# Signal_processing.net
KiCad netlist of a schematic drawn in EAGLE
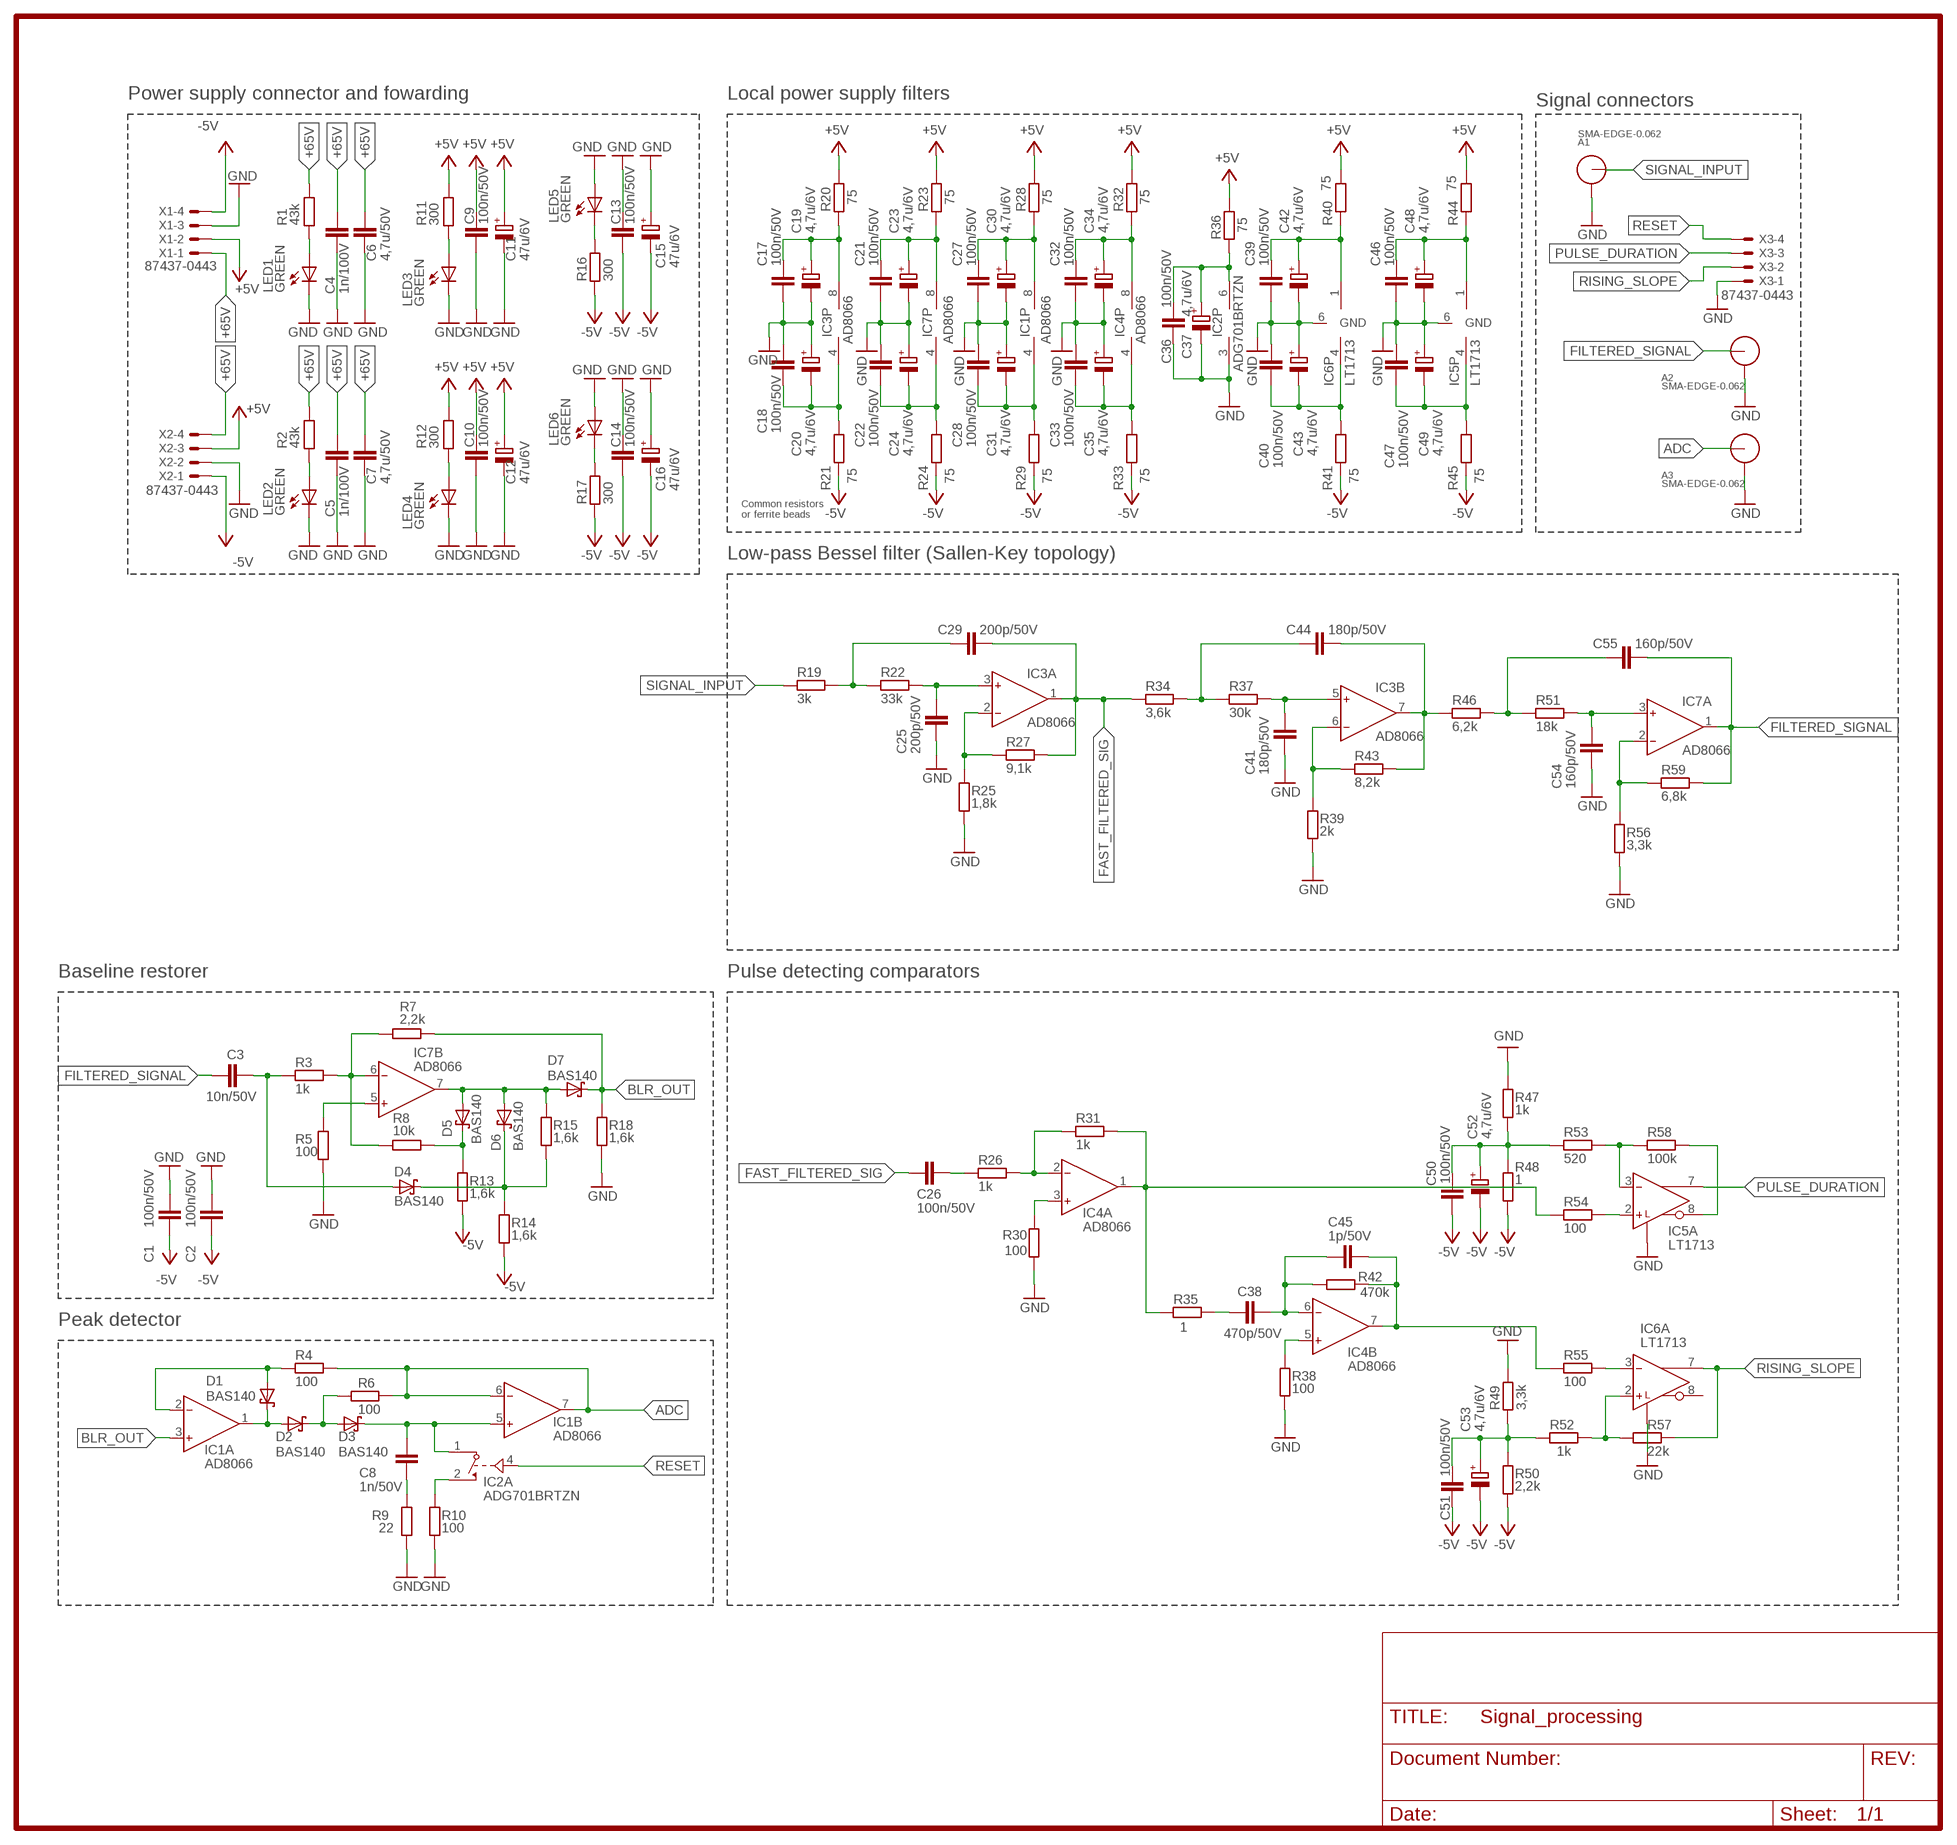
[diagram p0: schematic, sheet 1]

(export (version "E")
  (design (tool "Eeschema 10.0.6"))
  (components
    (comp (ref "A1")
      (value "SMA-EDGE-0.062")
      (footprint "eagle-import:CONSMA003.062")
      (libsource (lib "eagle-import") (part "LINX-SMA-EDGE-0.062"))
    )
    (comp (ref "A2")
      (value "SMA-EDGE-0.062")
      (footprint "eagle-import:CONSMA003.062")
      (libsource (lib "eagle-import") (part "LINX-SMA-EDGE-0.062"))
    )
    (comp (ref "A3")
      (value "SMA-EDGE-0.062")
      (footprint "eagle-import:CONSMA003.062")
      (libsource (lib "eagle-import") (part "LINX-SMA-EDGE-0.062"))
    )
    (comp (ref "C1")
      (value "100n/50V")
      (footprint "eagle-import:C0603")
      (libsource (lib "eagle-import") (part "rcl_334_C-EUC0603"))
    )
    (comp (ref "C2")
      (value "100n/50V")
      (footprint "eagle-import:C0603")
      (libsource (lib "eagle-import") (part "rcl_334_C-EUC0603"))
    )
    (comp (ref "C3")
      (value "10n/50V")
      (footprint "eagle-import:C0603")
      (libsource (lib "eagle-import") (part "rcl_334_C-EUC0603"))
    )
    (comp (ref "C4")
      (value "1n/100V")
      (footprint "eagle-import:C0603")
      (libsource (lib "eagle-import") (part "C-EUC0603"))
    )
    (comp (ref "C5")
      (value "1n/100V")
      (footprint "eagle-import:C0603")
      (libsource (lib "eagle-import") (part "C-EUC0603"))
    )
    (comp (ref "C6")
      (value "4,7u/50V")
      (footprint "eagle-import:C1206")
      (libsource (lib "eagle-import") (part "rcl_334_C-EUC1206"))
    )
    (comp (ref "C7")
      (value "4,7u/50V")
      (footprint "eagle-import:C1206")
      (libsource (lib "eagle-import") (part "rcl_334_C-EUC1206"))
    )
    (comp (ref "C8")
      (value "1n/50V")
      (footprint "eagle-import:C0603")
      (libsource (lib "eagle-import") (part "rcl_334_C-EUC0603"))
    )
    (comp (ref "C9")
      (value "100n/50V")
      (footprint "eagle-import:C0603")
      (libsource (lib "eagle-import") (part "rcl_334_C-EUC0603"))
    )
    (comp (ref "C10")
      (value "100n/50V")
      (footprint "eagle-import:C0603")
      (libsource (lib "eagle-import") (part "rcl_334_C-EUC0603"))
    )
    (comp (ref "C11")
      (value "47u/6V")
      (footprint "eagle-import:SMC_B")
      (libsource (lib "eagle-import") (part "CPOL-EUSMCB"))
    )
    (comp (ref "C12")
      (value "47u/6V")
      (footprint "eagle-import:SMC_B")
      (libsource (lib "eagle-import") (part "CPOL-EUSMCB"))
    )
    (comp (ref "C13")
      (value "100n/50V")
      (footprint "eagle-import:C0603")
      (libsource (lib "eagle-import") (part "rcl_334_C-EUC0603"))
    )
    (comp (ref "C14")
      (value "100n/50V")
      (footprint "eagle-import:C0603")
      (libsource (lib "eagle-import") (part "rcl_334_C-EUC0603"))
    )
    (comp (ref "C15")
      (value "47u/6V")
      (footprint "eagle-import:SMC_B")
      (libsource (lib "eagle-import") (part "CPOL-EUSMCB"))
    )
    (comp (ref "C16")
      (value "47u/6V")
      (footprint "eagle-import:SMC_B")
      (libsource (lib "eagle-import") (part "CPOL-EUSMCB"))
    )
    (comp (ref "C17")
      (value "100n/50V")
      (footprint "eagle-import:C0603")
      (libsource (lib "eagle-import") (part "rcl_334_C-EUC0603"))
    )
    (comp (ref "C18")
      (value "100n/50V")
      (footprint "eagle-import:C0603")
      (libsource (lib "eagle-import") (part "rcl_334_C-EUC0603"))
    )
    (comp (ref "C19")
      (value "4,7u/6V")
      (footprint "eagle-import:SMC_A")
      (libsource (lib "eagle-import") (part "CPOL-EUSMCA"))
    )
    (comp (ref "C20")
      (value "4,7u/6V")
      (footprint "eagle-import:SMC_A")
      (libsource (lib "eagle-import") (part "CPOL-EUSMCA"))
    )
    (comp (ref "C21")
      (value "100n/50V")
      (footprint "eagle-import:C0603")
      (libsource (lib "eagle-import") (part "rcl_334_C-EUC0603"))
    )
    (comp (ref "C22")
      (value "100n/50V")
      (footprint "eagle-import:C0603")
      (libsource (lib "eagle-import") (part "rcl_334_C-EUC0603"))
    )
    (comp (ref "C23")
      (value "4,7u/6V")
      (footprint "eagle-import:SMC_A")
      (libsource (lib "eagle-import") (part "CPOL-EUSMCA"))
    )
    (comp (ref "C24")
      (value "4,7u/6V")
      (footprint "eagle-import:SMC_A")
      (libsource (lib "eagle-import") (part "CPOL-EUSMCA"))
    )
    (comp (ref "C25")
      (value "200p/50V")
      (footprint "eagle-import:C0603")
      (libsource (lib "eagle-import") (part "rcl_334_C-EUC0603"))
    )
    (comp (ref "C26")
      (value "100n/50V")
      (footprint "eagle-import:C0603")
      (libsource (lib "eagle-import") (part "rcl_334_C-EUC0603"))
    )
    (comp (ref "C27")
      (value "100n/50V")
      (footprint "eagle-import:C0603")
      (libsource (lib "eagle-import") (part "rcl_334_C-EUC0603"))
    )
    (comp (ref "C28")
      (value "100n/50V")
      (footprint "eagle-import:C0603")
      (libsource (lib "eagle-import") (part "rcl_334_C-EUC0603"))
    )
    (comp (ref "C29")
      (value "200p/50V")
      (footprint "eagle-import:C0603")
      (libsource (lib "eagle-import") (part "rcl_334_C-EUC0603"))
    )
    (comp (ref "C30")
      (value "4,7u/6V")
      (footprint "eagle-import:SMC_A")
      (libsource (lib "eagle-import") (part "CPOL-EUSMCA"))
    )
    (comp (ref "C31")
      (value "4,7u/6V")
      (footprint "eagle-import:SMC_A")
      (libsource (lib "eagle-import") (part "CPOL-EUSMCA"))
    )
    (comp (ref "C32")
      (value "100n/50V")
      (footprint "eagle-import:C0603")
      (libsource (lib "eagle-import") (part "rcl_334_C-EUC0603"))
    )
    (comp (ref "C33")
      (value "100n/50V")
      (footprint "eagle-import:C0603")
      (libsource (lib "eagle-import") (part "rcl_334_C-EUC0603"))
    )
    (comp (ref "C34")
      (value "4,7u/6V")
      (footprint "eagle-import:SMC_A")
      (libsource (lib "eagle-import") (part "CPOL-EUSMCA"))
    )
    (comp (ref "C35")
      (value "4,7u/6V")
      (footprint "eagle-import:SMC_A")
      (libsource (lib "eagle-import") (part "CPOL-EUSMCA"))
    )
    (comp (ref "C36")
      (value "100n/50V")
      (footprint "eagle-import:C0603")
      (libsource (lib "eagle-import") (part "rcl_334_C-EUC0603"))
    )
    (comp (ref "C37")
      (value "4,7u/6V")
      (footprint "eagle-import:SMC_A")
      (libsource (lib "eagle-import") (part "CPOL-EUSMCA"))
    )
    (comp (ref "C38")
      (value "470p/50V")
      (footprint "eagle-import:C0603")
      (libsource (lib "eagle-import") (part "rcl_334_C-EUC0603"))
    )
    (comp (ref "C39")
      (value "100n/50V")
      (footprint "eagle-import:C0603")
      (libsource (lib "eagle-import") (part "rcl_334_C-EUC0603"))
    )
    (comp (ref "C40")
      (value "100n/50V")
      (footprint "eagle-import:C0603")
      (libsource (lib "eagle-import") (part "rcl_334_C-EUC0603"))
    )
    (comp (ref "C41")
      (value "180p/50V")
      (footprint "eagle-import:C0603")
      (libsource (lib "eagle-import") (part "rcl_334_C-EUC0603"))
    )
    (comp (ref "C42")
      (value "4,7u/6V")
      (footprint "eagle-import:SMC_A")
      (libsource (lib "eagle-import") (part "CPOL-EUSMCA"))
    )
    (comp (ref "C43")
      (value "4,7u/6V")
      (footprint "eagle-import:SMC_A")
      (libsource (lib "eagle-import") (part "CPOL-EUSMCA"))
    )
    (comp (ref "C44")
      (value "180p/50V")
      (footprint "eagle-import:C0603")
      (libsource (lib "eagle-import") (part "rcl_334_C-EUC0603"))
    )
    (comp (ref "C45")
      (value "1p/50V")
      (footprint "eagle-import:C0603")
      (libsource (lib "eagle-import") (part "rcl_334_C-EUC0603"))
    )
    (comp (ref "C46")
      (value "100n/50V")
      (footprint "eagle-import:C0603")
      (libsource (lib "eagle-import") (part "rcl_334_C-EUC0603"))
    )
    (comp (ref "C47")
      (value "100n/50V")
      (footprint "eagle-import:C0603")
      (libsource (lib "eagle-import") (part "rcl_334_C-EUC0603"))
    )
    (comp (ref "C48")
      (value "4,7u/6V")
      (footprint "eagle-import:SMC_A")
      (libsource (lib "eagle-import") (part "CPOL-EUSMCA"))
    )
    (comp (ref "C49")
      (value "4,7u/6V")
      (footprint "eagle-import:SMC_A")
      (libsource (lib "eagle-import") (part "CPOL-EUSMCA"))
    )
    (comp (ref "C50")
      (value "100n/50V")
      (footprint "eagle-import:C0603")
      (libsource (lib "eagle-import") (part "rcl_334_C-EUC0603"))
    )
    (comp (ref "C51")
      (value "100n/50V")
      (footprint "eagle-import:C0603")
      (libsource (lib "eagle-import") (part "rcl_334_C-EUC0603"))
    )
    (comp (ref "C52")
      (value "4,7u/6V")
      (footprint "eagle-import:SMC_A")
      (libsource (lib "eagle-import") (part "CPOL-EUSMCA"))
    )
    (comp (ref "C53")
      (value "4,7u/6V")
      (footprint "eagle-import:SMC_A")
      (libsource (lib "eagle-import") (part "CPOL-EUSMCA"))
    )
    (comp (ref "C54")
      (value "160p/50V")
      (footprint "eagle-import:C0603")
      (libsource (lib "eagle-import") (part "rcl_334_C-EUC0603"))
    )
    (comp (ref "C55")
      (value "160p/50V")
      (footprint "eagle-import:C0603")
      (libsource (lib "eagle-import") (part "rcl_334_C-EUC0603"))
    )
    (comp (ref "D1")
      (value "BAS140")
      (footprint "eagle-import:SOD2514X100N")
      (libsource (lib "eagle-import") (part "BAS140"))
    )
    (comp (ref "D2")
      (value "BAS140")
      (footprint "eagle-import:SOD2514X100N")
      (libsource (lib "eagle-import") (part "BAS140"))
    )
    (comp (ref "D3")
      (value "BAS140")
      (footprint "eagle-import:SOD2514X100N")
      (libsource (lib "eagle-import") (part "BAS140"))
    )
    (comp (ref "D4")
      (value "BAS140")
      (footprint "eagle-import:SOD2514X100N")
      (libsource (lib "eagle-import") (part "BAS140"))
    )
    (comp (ref "D5")
      (value "BAS140")
      (footprint "eagle-import:SOD2514X100N")
      (libsource (lib "eagle-import") (part "BAS140"))
    )
    (comp (ref "D6")
      (value "BAS140")
      (footprint "eagle-import:SOD2514X100N")
      (libsource (lib "eagle-import") (part "BAS140"))
    )
    (comp (ref "D7")
      (value "BAS140")
      (footprint "eagle-import:SOD2514X100N")
      (libsource (lib "eagle-import") (part "BAS140"))
    )
    (comp (ref "IC1")
      (value "AD8066")
      (footprint "eagle-import:MSOP8")
      (libsource (lib "eagle-import") (part "AD8066"))
    )
    (comp (ref "IC2")
      (value "ADG701BRTZN")
      (footprint "eagle-import:SOT23-6")
      (libsource (lib "eagle-import") (part "ADG701BRTZN"))
    )
    (comp (ref "IC3")
      (value "AD8066")
      (footprint "eagle-import:MSOP8")
      (libsource (lib "eagle-import") (part "AD8066"))
    )
    (comp (ref "IC4")
      (value "AD8066")
      (footprint "eagle-import:MSOP8")
      (libsource (lib "eagle-import") (part "AD8066"))
    )
    (comp (ref "IC5")
      (value "LT1713")
      (footprint "eagle-import:MSOP8")
      (libsource (lib "eagle-import") (part "LT1713"))
    )
    (comp (ref "IC6")
      (value "LT1713")
      (footprint "eagle-import:MSOP8")
      (libsource (lib "eagle-import") (part "LT1713"))
    )
    (comp (ref "IC7")
      (value "AD8066")
      (footprint "eagle-import:MSOP8")
      (libsource (lib "eagle-import") (part "AD8066"))
    )
    (comp (ref "LED1")
      (value "GREEN")
      (footprint "eagle-import:CHIPLED_0603")
      (libsource (lib "eagle-import") (part "LEDCHIPLED_0603"))
    )
    (comp (ref "LED2")
      (value "GREEN")
      (footprint "eagle-import:CHIPLED_0603")
      (libsource (lib "eagle-import") (part "LEDCHIPLED_0603"))
    )
    (comp (ref "LED3")
      (value "GREEN")
      (footprint "eagle-import:CHIPLED_0603")
      (libsource (lib "eagle-import") (part "LEDCHIPLED_0603"))
    )
    (comp (ref "LED4")
      (value "GREEN")
      (footprint "eagle-import:CHIPLED_0603")
      (libsource (lib "eagle-import") (part "LEDCHIPLED_0603"))
    )
    (comp (ref "LED5")
      (value "GREEN")
      (footprint "eagle-import:CHIPLED_0603")
      (libsource (lib "eagle-import") (part "LEDCHIPLED_0603"))
    )
    (comp (ref "LED6")
      (value "GREEN")
      (footprint "eagle-import:CHIPLED_0603")
      (libsource (lib "eagle-import") (part "LEDCHIPLED_0603"))
    )
    (comp (ref "R1")
      (value "43k")
      (footprint "eagle-import:R0603")
      (libsource (lib "eagle-import") (part "R-EU_R0603"))
    )
    (comp (ref "R2")
      (value "43k")
      (footprint "eagle-import:R0603")
      (libsource (lib "eagle-import") (part "R-EU_R0603"))
    )
    (comp (ref "R3")
      (value "1k")
      (footprint "eagle-import:R0603")
      (libsource (lib "eagle-import") (part "R-EU_R0603"))
    )
    (comp (ref "R4")
      (value "100")
      (footprint "eagle-import:R0603")
      (libsource (lib "eagle-import") (part "R-EU_R0603"))
    )
    (comp (ref "R5")
      (value "100")
      (footprint "eagle-import:R0603")
      (libsource (lib "eagle-import") (part "R-EU_R0603"))
    )
    (comp (ref "R6")
      (value "100")
      (footprint "eagle-import:R0603")
      (libsource (lib "eagle-import") (part "R-EU_R0603"))
    )
    (comp (ref "R7")
      (value "2,2k")
      (footprint "eagle-import:R0603")
      (libsource (lib "eagle-import") (part "R-EU_R0603"))
    )
    (comp (ref "R8")
      (value "10k")
      (footprint "eagle-import:R0603")
      (libsource (lib "eagle-import") (part "R-EU_R0603"))
    )
    (comp (ref "R9")
      (value "22")
      (footprint "eagle-import:R0603")
      (libsource (lib "eagle-import") (part "R-EU_R0603"))
    )
    (comp (ref "R10")
      (value "100")
      (footprint "eagle-import:R0603")
      (libsource (lib "eagle-import") (part "R-EU_R0603"))
    )
    (comp (ref "R11")
      (value "300")
      (footprint "eagle-import:R0603")
      (libsource (lib "eagle-import") (part "R-EU_R0603"))
    )
    (comp (ref "R12")
      (value "300")
      (footprint "eagle-import:R0603")
      (libsource (lib "eagle-import") (part "R-EU_R0603"))
    )
    (comp (ref "R13")
      (value "1,6k")
      (footprint "eagle-import:R0603")
      (libsource (lib "eagle-import") (part "R-EU_R0603"))
    )
    (comp (ref "R14")
      (value "1,6k")
      (footprint "eagle-import:R0603")
      (libsource (lib "eagle-import") (part "R-EU_R0603"))
    )
    (comp (ref "R15")
      (value "1,6k")
      (footprint "eagle-import:R0603")
      (libsource (lib "eagle-import") (part "R-EU_R0603"))
    )
    (comp (ref "R16")
      (value "300")
      (footprint "eagle-import:R0603")
      (libsource (lib "eagle-import") (part "R-EU_R0603"))
    )
    (comp (ref "R17")
      (value "300")
      (footprint "eagle-import:R0603")
      (libsource (lib "eagle-import") (part "R-EU_R0603"))
    )
    (comp (ref "R18")
      (value "1,6k")
      (footprint "eagle-import:R0603")
      (libsource (lib "eagle-import") (part "R-EU_R0603"))
    )
    (comp (ref "R19")
      (value "3k")
      (footprint "eagle-import:R0603")
      (libsource (lib "eagle-import") (part "R-EU_R0603"))
    )
    (comp (ref "R20")
      (value "75")
      (footprint "eagle-import:R0603")
      (libsource (lib "eagle-import") (part "R-EU_R0603"))
    )
    (comp (ref "R21")
      (value "75")
      (footprint "eagle-import:R0603")
      (libsource (lib "eagle-import") (part "R-EU_R0603"))
    )
    (comp (ref "R22")
      (value "33k")
      (footprint "eagle-import:R0603")
      (libsource (lib "eagle-import") (part "R-EU_R0603"))
    )
    (comp (ref "R23")
      (value "75")
      (footprint "eagle-import:R0603")
      (libsource (lib "eagle-import") (part "R-EU_R0603"))
    )
    (comp (ref "R24")
      (value "75")
      (footprint "eagle-import:R0603")
      (libsource (lib "eagle-import") (part "R-EU_R0603"))
    )
    (comp (ref "R25")
      (value "1,8k")
      (footprint "eagle-import:R0603")
      (libsource (lib "eagle-import") (part "R-EU_R0603"))
    )
    (comp (ref "R26")
      (value "1k")
      (footprint "eagle-import:R0603")
      (libsource (lib "eagle-import") (part "R-EU_R0603"))
    )
    (comp (ref "R27")
      (value "9,1k")
      (footprint "eagle-import:R0603")
      (libsource (lib "eagle-import") (part "R-EU_R0603"))
    )
    (comp (ref "R28")
      (value "75")
      (footprint "eagle-import:R0603")
      (libsource (lib "eagle-import") (part "R-EU_R0603"))
    )
    (comp (ref "R29")
      (value "75")
      (footprint "eagle-import:R0603")
      (libsource (lib "eagle-import") (part "R-EU_R0603"))
    )
    (comp (ref "R30")
      (value "100")
      (footprint "eagle-import:R0603")
      (libsource (lib "eagle-import") (part "R-EU_R0603"))
    )
    (comp (ref "R31")
      (value "1k")
      (footprint "eagle-import:R0603")
      (libsource (lib "eagle-import") (part "R-EU_R0603"))
    )
    (comp (ref "R32")
      (value "75")
      (footprint "eagle-import:R0603")
      (libsource (lib "eagle-import") (part "R-EU_R0603"))
    )
    (comp (ref "R33")
      (value "75")
      (footprint "eagle-import:R0603")
      (libsource (lib "eagle-import") (part "R-EU_R0603"))
    )
    (comp (ref "R34")
      (value "3,6k")
      (footprint "eagle-import:R0603")
      (libsource (lib "eagle-import") (part "R-EU_R0603"))
    )
    (comp (ref "R35")
      (value "1")
      (footprint "eagle-import:R0603")
      (libsource (lib "eagle-import") (part "R-EU_R0603"))
    )
    (comp (ref "R36")
      (value "75")
      (footprint "eagle-import:R0603")
      (libsource (lib "eagle-import") (part "R-EU_R0603"))
    )
    (comp (ref "R37")
      (value "30k")
      (footprint "eagle-import:R0603")
      (libsource (lib "eagle-import") (part "R-EU_R0603"))
    )
    (comp (ref "R38")
      (value "100")
      (footprint "eagle-import:R0603")
      (libsource (lib "eagle-import") (part "R-EU_R0603"))
    )
    (comp (ref "R39")
      (value "2k")
      (footprint "eagle-import:R0603")
      (libsource (lib "eagle-import") (part "R-EU_R0603"))
    )
    (comp (ref "R40")
      (value "75")
      (footprint "eagle-import:R0603")
      (libsource (lib "eagle-import") (part "R-EU_R0603"))
    )
    (comp (ref "R41")
      (value "75")
      (footprint "eagle-import:R0603")
      (libsource (lib "eagle-import") (part "R-EU_R0603"))
    )
    (comp (ref "R42")
      (value "470k")
      (footprint "eagle-import:R0603")
      (libsource (lib "eagle-import") (part "R-EU_R0603"))
    )
    (comp (ref "R43")
      (value "8,2k")
      (footprint "eagle-import:R0603")
      (libsource (lib "eagle-import") (part "R-EU_R0603"))
    )
    (comp (ref "R44")
      (value "75")
      (footprint "eagle-import:R0603")
      (libsource (lib "eagle-import") (part "R-EU_R0603"))
    )
    (comp (ref "R45")
      (value "75")
      (footprint "eagle-import:R0603")
      (libsource (lib "eagle-import") (part "R-EU_R0603"))
    )
    (comp (ref "R46")
      (value "6,2k")
      (footprint "eagle-import:R0603")
      (libsource (lib "eagle-import") (part "R-EU_R0603"))
    )
    (comp (ref "R47")
      (value "1k")
      (footprint "eagle-import:R0603")
      (libsource (lib "eagle-import") (part "R-EU_R0603"))
    )
    (comp (ref "R48")
      (value "1")
      (footprint "eagle-import:R0603")
      (libsource (lib "eagle-import") (part "R-EU_R0603"))
    )
    (comp (ref "R49")
      (value "3,3k")
      (footprint "eagle-import:R0603")
      (libsource (lib "eagle-import") (part "R-EU_R0603"))
    )
    (comp (ref "R50")
      (value "2,2k")
      (footprint "eagle-import:R0603")
      (libsource (lib "eagle-import") (part "R-EU_R0603"))
    )
    (comp (ref "R51")
      (value "18k")
      (footprint "eagle-import:R0603")
      (libsource (lib "eagle-import") (part "R-EU_R0603"))
    )
    (comp (ref "R52")
      (value "1k")
      (footprint "eagle-import:R0603")
      (libsource (lib "eagle-import") (part "R-EU_R0603"))
    )
    (comp (ref "R53")
      (value "520")
      (footprint "eagle-import:R0603")
      (libsource (lib "eagle-import") (part "R-EU_R0603"))
    )
    (comp (ref "R54")
      (value "100")
      (footprint "eagle-import:R0603")
      (libsource (lib "eagle-import") (part "R-EU_R0603"))
    )
    (comp (ref "R55")
      (value "100")
      (footprint "eagle-import:R0603")
      (libsource (lib "eagle-import") (part "R-EU_R0603"))
    )
    (comp (ref "R56")
      (value "3,3k")
      (footprint "eagle-import:R0603")
      (libsource (lib "eagle-import") (part "R-EU_R0603"))
    )
    (comp (ref "R57")
      (value "22k")
      (footprint "eagle-import:R0603")
      (libsource (lib "eagle-import") (part "R-EU_R0603"))
    )
    (comp (ref "R58")
      (value "100k")
      (footprint "eagle-import:R0603")
      (libsource (lib "eagle-import") (part "R-EU_R0603"))
    )
    (comp (ref "R59")
      (value "6,8k")
      (footprint "eagle-import:R0603")
      (libsource (lib "eagle-import") (part "R-EU_R0603"))
    )
    (comp (ref "X1")
      (value "87437-0443")
      (footprint "eagle-import:87437-0443")
      (libsource (lib "eagle-import") (part "87438-0487437-0443"))
    )
    (comp (ref "X2")
      (value "87437-0443")
      (footprint "eagle-import:87437-0443")
      (libsource (lib "eagle-import") (part "87438-0487437-0443"))
    )
    (comp (ref "X3")
      (value "87437-0443")
      (footprint "eagle-import:87437-0443")
      (libsource (lib "eagle-import") (part "87438-0487437-0443"))
    )
  )
  (nets
    (net (code "1") (name "+5V") (class "Default")
      (node (ref "C10") (pin "2") (pinfunction "2_2") (pintype "passive"))
      (node (ref "C11") (pin "+") (pinfunction "+_+") (pintype "passive"))
      (node (ref "C12") (pin "+") (pinfunction "+_+") (pintype "passive"))
      (node (ref "C9") (pin "2") (pinfunction "2_2") (pintype "passive"))
      (node (ref "R11") (pin "2") (pinfunction "2_2") (pintype "passive"))
      (node (ref "R12") (pin "2") (pinfunction "2_2") (pintype "passive"))
      (node (ref "R20") (pin "1") (pinfunction "1_1") (pintype "passive"))
      (node (ref "R23") (pin "1") (pinfunction "1_1") (pintype "passive"))
      (node (ref "R28") (pin "1") (pinfunction "1_1") (pintype "passive"))
      (node (ref "R32") (pin "1") (pinfunction "1_1") (pintype "passive"))
      (node (ref "R36") (pin "1") (pinfunction "1_1") (pintype "passive"))
      (node (ref "R40") (pin "1") (pinfunction "1_1") (pintype "passive"))
      (node (ref "R44") (pin "1") (pinfunction "1_1") (pintype "passive"))
      (node (ref "X1") (pin "2") (pinfunction "S_2") (pintype "passive"))
      (node (ref "X1") (pin "6") (pinfunction "S_6") (pintype "passive"))
      (node (ref "X2") (pin "3") (pinfunction "S_3") (pintype "passive"))
      (node (ref "X2") (pin "7") (pinfunction "S_7") (pintype "passive"))
    )
    (net (code "2") (name "+65V") (class "Default")
      (node (ref "C4") (pin "2") (pinfunction "2_2") (pintype "passive"))
      (node (ref "C5") (pin "2") (pinfunction "2_2") (pintype "passive"))
      (node (ref "C6") (pin "1") (pinfunction "1_1") (pintype "passive"))
      (node (ref "C7") (pin "1") (pinfunction "1_1") (pintype "passive"))
      (node (ref "R1") (pin "2") (pinfunction "2_2") (pintype "passive"))
      (node (ref "R2") (pin "2") (pinfunction "2_2") (pintype "passive"))
      (node (ref "X1") (pin "1") (pinfunction "S_1") (pintype "passive"))
      (node (ref "X1") (pin "5") (pinfunction "S_5") (pintype "passive"))
      (node (ref "X2") (pin "4") (pinfunction "S_4") (pintype "passive"))
      (node (ref "X2") (pin "8") (pinfunction "S_8") (pintype "passive"))
    )
    (net (code "3") (name "-5V") (class "Default")
      (node (ref "C1") (pin "1") (pinfunction "1_1") (pintype "passive"))
      (node (ref "C13") (pin "1") (pinfunction "1_1") (pintype "passive"))
      (node (ref "C14") (pin "1") (pinfunction "1_1") (pintype "passive"))
      (node (ref "C15") (pin "-") (pinfunction "-_-") (pintype "passive"))
      (node (ref "C16") (pin "-") (pinfunction "-_-") (pintype "passive"))
      (node (ref "C2") (pin "1") (pinfunction "1_1") (pintype "passive"))
      (node (ref "C50") (pin "2") (pinfunction "2_2") (pintype "passive"))
      (node (ref "C51") (pin "2") (pinfunction "2_2") (pintype "passive"))
      (node (ref "C52") (pin "-") (pinfunction "-_-") (pintype "passive"))
      (node (ref "C53") (pin "-") (pinfunction "-_-") (pintype "passive"))
      (node (ref "R13") (pin "2") (pinfunction "2_2") (pintype "passive"))
      (node (ref "R14") (pin "2") (pinfunction "2_2") (pintype "passive"))
      (node (ref "R16") (pin "1") (pinfunction "1_1") (pintype "passive"))
      (node (ref "R17") (pin "1") (pinfunction "1_1") (pintype "passive"))
      (node (ref "R21") (pin "2") (pinfunction "2_2") (pintype "passive"))
      (node (ref "R24") (pin "2") (pinfunction "2_2") (pintype "passive"))
      (node (ref "R29") (pin "2") (pinfunction "2_2") (pintype "passive"))
      (node (ref "R33") (pin "2") (pinfunction "2_2") (pintype "passive"))
      (node (ref "R41") (pin "2") (pinfunction "2_2") (pintype "passive"))
      (node (ref "R45") (pin "2") (pinfunction "2_2") (pintype "passive"))
      (node (ref "R48") (pin "2") (pinfunction "2_2") (pintype "passive"))
      (node (ref "R50") (pin "2") (pinfunction "2_2") (pintype "passive"))
      (node (ref "X1") (pin "4") (pinfunction "S_4") (pintype "passive"))
      (node (ref "X1") (pin "8") (pinfunction "S_8") (pintype "passive"))
      (node (ref "X2") (pin "1") (pinfunction "S_1") (pintype "passive"))
      (node (ref "X2") (pin "5") (pinfunction "S_5") (pintype "passive"))
    )
    (net (code "4") (name "ADC") (class "Default")
      (node (ref "A3") (pin "ANT") (pinfunction "ANT_ANT") (pintype "bidirectional"))
      (node (ref "IC1") (pin "6") (pinfunction "IN-_6") (pintype "input"))
      (node (ref "IC1") (pin "7") (pinfunction "OUT_7") (pintype "output"))
      (node (ref "R4") (pin "2") (pinfunction "2_2") (pintype "passive"))
      (node (ref "R6") (pin "2") (pinfunction "2_2") (pintype "passive"))
    )
    (net (code "5") (name "BLR_OUT") (class "Default")
      (node (ref "D7") (pin "K") (pinfunction "K_K") (pintype "passive"))
      (node (ref "IC1") (pin "3") (pinfunction "IN+_3") (pintype "input"))
      (node (ref "R18") (pin "1") (pinfunction "1_1") (pintype "passive"))
      (node (ref "R7") (pin "1") (pinfunction "1_1") (pintype "passive"))
    )
    (net (code "6") (name "FAST_FILTERED_SIG") (class "Default")
      (node (ref "C26") (pin "2") (pinfunction "2_2") (pintype "passive"))
      (node (ref "C29") (pin "1") (pinfunction "1_1") (pintype "passive"))
      (node (ref "IC3") (pin "1") (pinfunction "OUT_1") (pintype "output"))
      (node (ref "R27") (pin "2") (pinfunction "2_2") (pintype "passive"))
      (node (ref "R34") (pin "1") (pinfunction "1_1") (pintype "passive"))
    )
    (net (code "7") (name "FILTERED_SIGNAL") (class "Default")
      (node (ref "A2") (pin "ANT") (pinfunction "ANT_ANT") (pintype "bidirectional"))
      (node (ref "C3") (pin "2") (pinfunction "2_2") (pintype "passive"))
      (node (ref "C55") (pin "1") (pinfunction "1_1") (pintype "passive"))
      (node (ref "IC7") (pin "1") (pinfunction "OUT_1") (pintype "output"))
      (node (ref "R59") (pin "2") (pinfunction "2_2") (pintype "passive"))
    )
    (net (code "8") (name "GND") (class "Default")
      (node (ref "A1") (pin "GND1") (pinfunction "P$2_GND1") (pintype "bidirectional"))
      (node (ref "A1") (pin "GND2") (pinfunction "P$2_GND2") (pintype "bidirectional"))
      (node (ref "A1") (pin "GND3") (pinfunction "P$2_GND3") (pintype "bidirectional"))
      (node (ref "A1") (pin "GND4") (pinfunction "P$2_GND4") (pintype "bidirectional"))
      (node (ref "A2") (pin "GND1") (pinfunction "P$2_GND1") (pintype "bidirectional"))
      (node (ref "A2") (pin "GND2") (pinfunction "P$2_GND2") (pintype "bidirectional"))
      (node (ref "A2") (pin "GND3") (pinfunction "P$2_GND3") (pintype "bidirectional"))
      (node (ref "A2") (pin "GND4") (pinfunction "P$2_GND4") (pintype "bidirectional"))
      (node (ref "A3") (pin "GND1") (pinfunction "P$2_GND1") (pintype "bidirectional"))
      (node (ref "A3") (pin "GND2") (pinfunction "P$2_GND2") (pintype "bidirectional"))
      (node (ref "A3") (pin "GND3") (pinfunction "P$2_GND3") (pintype "bidirectional"))
      (node (ref "A3") (pin "GND4") (pinfunction "P$2_GND4") (pintype "bidirectional"))
      (node (ref "C1") (pin "2") (pinfunction "2_2") (pintype "passive"))
      (node (ref "C10") (pin "1") (pinfunction "1_1") (pintype "passive"))
      (node (ref "C11") (pin "-") (pinfunction "-_-") (pintype "passive"))
      (node (ref "C12") (pin "-") (pinfunction "-_-") (pintype "passive"))
      (node (ref "C13") (pin "2") (pinfunction "2_2") (pintype "passive"))
      (node (ref "C14") (pin "2") (pinfunction "2_2") (pintype "passive"))
      (node (ref "C15") (pin "+") (pinfunction "+_+") (pintype "passive"))
      (node (ref "C16") (pin "+") (pinfunction "+_+") (pintype "passive"))
      (node (ref "C17") (pin "1") (pinfunction "1_1") (pintype "passive"))
      (node (ref "C18") (pin "2") (pinfunction "2_2") (pintype "passive"))
      (node (ref "C19") (pin "-") (pinfunction "-_-") (pintype "passive"))
      (node (ref "C2") (pin "2") (pinfunction "2_2") (pintype "passive"))
      (node (ref "C20") (pin "+") (pinfunction "+_+") (pintype "passive"))
      (node (ref "C21") (pin "1") (pinfunction "1_1") (pintype "passive"))
      (node (ref "C22") (pin "2") (pinfunction "2_2") (pintype "passive"))
      (node (ref "C23") (pin "-") (pinfunction "-_-") (pintype "passive"))
      (node (ref "C24") (pin "+") (pinfunction "+_+") (pintype "passive"))
      (node (ref "C25") (pin "1") (pinfunction "1_1") (pintype "passive"))
      (node (ref "C27") (pin "1") (pinfunction "1_1") (pintype "passive"))
      (node (ref "C28") (pin "2") (pinfunction "2_2") (pintype "passive"))
      (node (ref "C30") (pin "-") (pinfunction "-_-") (pintype "passive"))
      (node (ref "C31") (pin "+") (pinfunction "+_+") (pintype "passive"))
      (node (ref "C32") (pin "1") (pinfunction "1_1") (pintype "passive"))
      (node (ref "C33") (pin "2") (pinfunction "2_2") (pintype "passive"))
      (node (ref "C34") (pin "-") (pinfunction "-_-") (pintype "passive"))
      (node (ref "C35") (pin "+") (pinfunction "+_+") (pintype "passive"))
      (node (ref "C36") (pin "1") (pinfunction "1_1") (pintype "passive"))
      (node (ref "C37") (pin "-") (pinfunction "-_-") (pintype "passive"))
      (node (ref "C39") (pin "1") (pinfunction "1_1") (pintype "passive"))
      (node (ref "C4") (pin "1") (pinfunction "1_1") (pintype "passive"))
      (node (ref "C40") (pin "2") (pinfunction "2_2") (pintype "passive"))
      (node (ref "C41") (pin "1") (pinfunction "1_1") (pintype "passive"))
      (node (ref "C42") (pin "-") (pinfunction "-_-") (pintype "passive"))
      (node (ref "C43") (pin "+") (pinfunction "+_+") (pintype "passive"))
      (node (ref "C46") (pin "1") (pinfunction "1_1") (pintype "passive"))
      (node (ref "C47") (pin "2") (pinfunction "2_2") (pintype "passive"))
      (node (ref "C48") (pin "-") (pinfunction "-_-") (pintype "passive"))
      (node (ref "C49") (pin "+") (pinfunction "+_+") (pintype "passive"))
      (node (ref "C5") (pin "1") (pinfunction "1_1") (pintype "passive"))
      (node (ref "C54") (pin "1") (pinfunction "1_1") (pintype "passive"))
      (node (ref "C6") (pin "2") (pinfunction "2_2") (pintype "passive"))
      (node (ref "C7") (pin "2") (pinfunction "2_2") (pintype "passive"))
      (node (ref "C9") (pin "1") (pinfunction "1_1") (pintype "passive"))
      (node (ref "IC2") (pin "3") (pinfunction "V-_3") (pintype "power_in"))
      (node (ref "IC5") (pin "5") (pinfunction "L_5") (pintype "input"))
      (node (ref "IC5") (pin "6") (pinfunction "GND_6") (pintype "power_in"))
      (node (ref "IC6") (pin "5") (pinfunction "L_5") (pintype "input"))
      (node (ref "IC6") (pin "6") (pinfunction "GND_6") (pintype "power_in"))
      (node (ref "LED1") (pin "C") (pinfunction "C_C") (pintype "passive"))
      (node (ref "LED2") (pin "C") (pinfunction "C_C") (pintype "passive"))
      (node (ref "LED3") (pin "C") (pinfunction "C_C") (pintype "passive"))
      (node (ref "LED4") (pin "C") (pinfunction "C_C") (pintype "passive"))
      (node (ref "LED5") (pin "A") (pinfunction "A_A") (pintype "passive"))
      (node (ref "LED6") (pin "A") (pinfunction "A_A") (pintype "passive"))
      (node (ref "R10") (pin "1") (pinfunction "1_1") (pintype "passive"))
      (node (ref "R18") (pin "2") (pinfunction "2_2") (pintype "passive"))
      (node (ref "R25") (pin "1") (pinfunction "1_1") (pintype "passive"))
      (node (ref "R30") (pin "1") (pinfunction "1_1") (pintype "passive"))
      (node (ref "R38") (pin "1") (pinfunction "1_1") (pintype "passive"))
      (node (ref "R39") (pin "1") (pinfunction "1_1") (pintype "passive"))
      (node (ref "R47") (pin "1") (pinfunction "1_1") (pintype "passive"))
      (node (ref "R49") (pin "1") (pinfunction "1_1") (pintype "passive"))
      (node (ref "R5") (pin "1") (pinfunction "1_1") (pintype "passive"))
      (node (ref "R56") (pin "1") (pinfunction "1_1") (pintype "passive"))
      (node (ref "R9") (pin "1") (pinfunction "1_1") (pintype "passive"))
      (node (ref "X1") (pin "3") (pinfunction "S_3") (pintype "passive"))
      (node (ref "X1") (pin "7") (pinfunction "S_7") (pintype "passive"))
      (node (ref "X2") (pin "2") (pinfunction "S_2") (pintype "passive"))
      (node (ref "X2") (pin "6") (pinfunction "S_6") (pintype "passive"))
      (node (ref "X3") (pin "1") (pinfunction "S_1") (pintype "passive"))
      (node (ref "X3") (pin "5") (pinfunction "S_5") (pintype "passive"))
    )
    (net (code "9") (name "Net-(C3-Pad1)") (class "Default")
      (node (ref "C3") (pin "1") (pinfunction "1_1") (pintype "passive"))
      (node (ref "D4") (pin "A") (pinfunction "A_A") (pintype "passive"))
      (node (ref "R3") (pin "1") (pinfunction "1_1") (pintype "passive"))
    )
    (net (code "10") (name "Net-(C8-Pad2)") (class "Default")
      (node (ref "C8") (pin "2") (pinfunction "2_2") (pintype "passive"))
      (node (ref "R9") (pin "2") (pinfunction "2_2") (pintype "passive"))
    )
    (net (code "11") (name "Net-(C26-Pad1)") (class "Default")
      (node (ref "C26") (pin "1") (pinfunction "1_1") (pintype "passive"))
      (node (ref "R26") (pin "1") (pinfunction "1_1") (pintype "passive"))
    )
    (net (code "12") (name "Net-(C29-Pad2)") (class "Default")
      (node (ref "C29") (pin "2") (pinfunction "2_2") (pintype "passive"))
      (node (ref "R19") (pin "2") (pinfunction "2_2") (pintype "passive"))
      (node (ref "R22") (pin "1") (pinfunction "1_1") (pintype "passive"))
    )
    (net (code "13") (name "Net-(C38-Pad2)") (class "Default")
      (node (ref "C38") (pin "2") (pinfunction "2_2") (pintype "passive"))
      (node (ref "R35") (pin "2") (pinfunction "2_2") (pintype "passive"))
    )
    (net (code "14") (name "Net-(C44-Pad2)") (class "Default")
      (node (ref "C44") (pin "2") (pinfunction "2_2") (pintype "passive"))
      (node (ref "R34") (pin "2") (pinfunction "2_2") (pintype "passive"))
      (node (ref "R37") (pin "1") (pinfunction "1_1") (pintype "passive"))
    )
    (net (code "15") (name "Net-(C50-Pad1)") (class "Default")
      (node (ref "C50") (pin "1") (pinfunction "1_1") (pintype "passive"))
      (node (ref "C52") (pin "+") (pinfunction "+_+") (pintype "passive"))
      (node (ref "R47") (pin "2") (pinfunction "2_2") (pintype "passive"))
      (node (ref "R48") (pin "1") (pinfunction "1_1") (pintype "passive"))
      (node (ref "R53") (pin "1") (pinfunction "1_1") (pintype "passive"))
    )
    (net (code "16") (name "Net-(C51-Pad1)") (class "Default")
      (node (ref "C51") (pin "1") (pinfunction "1_1") (pintype "passive"))
      (node (ref "C53") (pin "+") (pinfunction "+_+") (pintype "passive"))
      (node (ref "R49") (pin "2") (pinfunction "2_2") (pintype "passive"))
      (node (ref "R50") (pin "1") (pinfunction "1_1") (pintype "passive"))
      (node (ref "R52") (pin "1") (pinfunction "1_1") (pintype "passive"))
    )
    (net (code "17") (name "Net-(C55-Pad2)") (class "Default")
      (node (ref "C55") (pin "2") (pinfunction "2_2") (pintype "passive"))
      (node (ref "R46") (pin "2") (pinfunction "2_2") (pintype "passive"))
      (node (ref "R51") (pin "1") (pinfunction "1_1") (pintype "passive"))
    )
    (net (code "18") (name "Net-(D2-PadK)") (class "Default")
      (node (ref "D2") (pin "K") (pinfunction "K_K") (pintype "passive"))
      (node (ref "D3") (pin "A") (pinfunction "A_A") (pintype "passive"))
      (node (ref "R6") (pin "1") (pinfunction "1_1") (pintype "passive"))
    )
    (net (code "19") (name "Net-(D4-PadK)") (class "Default")
      (node (ref "D4") (pin "K") (pinfunction "K_K") (pintype "passive"))
      (node (ref "D6") (pin "K") (pinfunction "K_K") (pintype "passive"))
      (node (ref "R14") (pin "1") (pinfunction "1_1") (pintype "passive"))
      (node (ref "R15") (pin "2") (pinfunction "2_2") (pintype "passive"))
    )
    (net (code "20") (name "Net-(D5-PadK)") (class "Default")
      (node (ref "D5") (pin "K") (pinfunction "K_K") (pintype "passive"))
      (node (ref "R13") (pin "1") (pinfunction "1_1") (pintype "passive"))
      (node (ref "R8") (pin "1") (pinfunction "1_1") (pintype "passive"))
    )
    (net (code "21") (name "Net-(IC1A-IN-)") (class "Default")
      (node (ref "D1") (pin "A") (pinfunction "A_A") (pintype "passive"))
      (node (ref "IC1") (pin "2") (pinfunction "IN-_2") (pintype "input"))
      (node (ref "R4") (pin "1") (pinfunction "1_1") (pintype "passive"))
    )
    (net (code "22") (name "Net-(IC1A-OUT)") (class "Default")
      (node (ref "D1") (pin "K") (pinfunction "K_K") (pintype "passive"))
      (node (ref "D2") (pin "A") (pinfunction "A_A") (pintype "passive"))
      (node (ref "IC1") (pin "1") (pinfunction "OUT_1") (pintype "output"))
    )
    (net (code "23") (name "Net-(IC1B-IN+)") (class "Default")
      (node (ref "C8") (pin "1") (pinfunction "1_1") (pintype "passive"))
      (node (ref "D3") (pin "K") (pinfunction "K_K") (pintype "passive"))
      (node (ref "IC1") (pin "5") (pinfunction "IN+_5") (pintype "input"))
      (node (ref "IC2") (pin "1") (pinfunction "D_1") (pintype "passive"))
    )
    (net (code "24") (name "Net-(IC1C-V+)") (class "Default")
      (node (ref "C27") (pin "2") (pinfunction "2_2") (pintype "passive"))
      (node (ref "C30") (pin "+") (pinfunction "+_+") (pintype "passive"))
      (node (ref "IC1") (pin "8") (pinfunction "V+_8") (pintype "power_in"))
      (node (ref "R28") (pin "2") (pinfunction "2_2") (pintype "passive"))
    )
    (net (code "25") (name "Net-(IC1C-V-)") (class "Default")
      (node (ref "C28") (pin "1") (pinfunction "1_1") (pintype "passive"))
      (node (ref "C31") (pin "-") (pinfunction "-_-") (pintype "passive"))
      (node (ref "IC1") (pin "4") (pinfunction "V-_4") (pintype "power_in"))
      (node (ref "R29") (pin "1") (pinfunction "1_1") (pintype "passive"))
    )
    (net (code "26") (name "Net-(IC2A-S)") (class "Default")
      (node (ref "IC2") (pin "2") (pinfunction "S_2") (pintype "passive"))
      (node (ref "R10") (pin "2") (pinfunction "2_2") (pintype "passive"))
    )
    (net (code "27") (name "Net-(IC2B-V+)") (class "Default")
      (node (ref "C36") (pin "2") (pinfunction "2_2") (pintype "passive"))
      (node (ref "C37") (pin "+") (pinfunction "+_+") (pintype "passive"))
      (node (ref "IC2") (pin "6") (pinfunction "V+_6") (pintype "power_in"))
      (node (ref "R36") (pin "2") (pinfunction "2_2") (pintype "passive"))
    )
    (net (code "28") (name "Net-(IC3A-IN+)") (class "Default")
      (node (ref "C25") (pin "2") (pinfunction "2_2") (pintype "passive"))
      (node (ref "IC3") (pin "3") (pinfunction "IN+_3") (pintype "input"))
      (node (ref "R22") (pin "2") (pinfunction "2_2") (pintype "passive"))
    )
    (net (code "29") (name "Net-(IC3A-IN-)") (class "Default")
      (node (ref "IC3") (pin "2") (pinfunction "IN-_2") (pintype "input"))
      (node (ref "R25") (pin "2") (pinfunction "2_2") (pintype "passive"))
      (node (ref "R27") (pin "1") (pinfunction "1_1") (pintype "passive"))
    )
    (net (code "30") (name "Net-(IC3B-IN+)") (class "Default")
      (node (ref "C41") (pin "2") (pinfunction "2_2") (pintype "passive"))
      (node (ref "IC3") (pin "5") (pinfunction "IN+_5") (pintype "input"))
      (node (ref "R37") (pin "2") (pinfunction "2_2") (pintype "passive"))
    )
    (net (code "31") (name "Net-(IC3B-IN-)") (class "Default")
      (node (ref "IC3") (pin "6") (pinfunction "IN-_6") (pintype "input"))
      (node (ref "R39") (pin "2") (pinfunction "2_2") (pintype "passive"))
      (node (ref "R43") (pin "1") (pinfunction "1_1") (pintype "passive"))
    )
    (net (code "32") (name "Net-(IC3B-OUT)") (class "Default")
      (node (ref "C44") (pin "1") (pinfunction "1_1") (pintype "passive"))
      (node (ref "IC3") (pin "7") (pinfunction "OUT_7") (pintype "output"))
      (node (ref "R43") (pin "2") (pinfunction "2_2") (pintype "passive"))
      (node (ref "R46") (pin "1") (pinfunction "1_1") (pintype "passive"))
    )
    (net (code "33") (name "Net-(IC3C-V+)") (class "Default")
      (node (ref "C17") (pin "2") (pinfunction "2_2") (pintype "passive"))
      (node (ref "C19") (pin "+") (pinfunction "+_+") (pintype "passive"))
      (node (ref "IC3") (pin "8") (pinfunction "V+_8") (pintype "power_in"))
      (node (ref "R20") (pin "2") (pinfunction "2_2") (pintype "passive"))
    )
    (net (code "34") (name "Net-(IC3C-V-)") (class "Default")
      (node (ref "C18") (pin "1") (pinfunction "1_1") (pintype "passive"))
      (node (ref "C20") (pin "-") (pinfunction "-_-") (pintype "passive"))
      (node (ref "IC3") (pin "4") (pinfunction "V-_4") (pintype "power_in"))
      (node (ref "R21") (pin "1") (pinfunction "1_1") (pintype "passive"))
    )
    (net (code "35") (name "Net-(IC4A-IN+)") (class "Default")
      (node (ref "IC4") (pin "3") (pinfunction "IN+_3") (pintype "input"))
      (node (ref "R30") (pin "2") (pinfunction "2_2") (pintype "passive"))
    )
    (net (code "36") (name "Net-(IC4A-IN-)") (class "Default")
      (node (ref "IC4") (pin "2") (pinfunction "IN-_2") (pintype "input"))
      (node (ref "R26") (pin "2") (pinfunction "2_2") (pintype "passive"))
      (node (ref "R31") (pin "1") (pinfunction "1_1") (pintype "passive"))
    )
    (net (code "37") (name "Net-(IC4A-OUT)") (class "Default")
      (node (ref "IC4") (pin "1") (pinfunction "OUT_1") (pintype "output"))
      (node (ref "R31") (pin "2") (pinfunction "2_2") (pintype "passive"))
      (node (ref "R35") (pin "1") (pinfunction "1_1") (pintype "passive"))
      (node (ref "R54") (pin "1") (pinfunction "1_1") (pintype "passive"))
    )
    (net (code "38") (name "Net-(IC4B-IN+)") (class "Default")
      (node (ref "IC4") (pin "5") (pinfunction "IN+_5") (pintype "input"))
      (node (ref "R38") (pin "2") (pinfunction "2_2") (pintype "passive"))
    )
    (net (code "39") (name "Net-(IC4B-IN-)") (class "Default")
      (node (ref "C38") (pin "1") (pinfunction "1_1") (pintype "passive"))
      (node (ref "C45") (pin "2") (pinfunction "2_2") (pintype "passive"))
      (node (ref "IC4") (pin "6") (pinfunction "IN-_6") (pintype "input"))
      (node (ref "R42") (pin "1") (pinfunction "1_1") (pintype "passive"))
    )
    (net (code "40") (name "Net-(IC4B-OUT)") (class "Default")
      (node (ref "C45") (pin "1") (pinfunction "1_1") (pintype "passive"))
      (node (ref "IC4") (pin "7") (pinfunction "OUT_7") (pintype "output"))
      (node (ref "R42") (pin "2") (pinfunction "2_2") (pintype "passive"))
      (node (ref "R55") (pin "1") (pinfunction "1_1") (pintype "passive"))
    )
    (net (code "41") (name "Net-(IC4C-V+)") (class "Default")
      (node (ref "C32") (pin "2") (pinfunction "2_2") (pintype "passive"))
      (node (ref "C34") (pin "+") (pinfunction "+_+") (pintype "passive"))
      (node (ref "IC4") (pin "8") (pinfunction "V+_8") (pintype "power_in"))
      (node (ref "R32") (pin "2") (pinfunction "2_2") (pintype "passive"))
    )
    (net (code "42") (name "Net-(IC4C-V-)") (class "Default")
      (node (ref "C33") (pin "1") (pinfunction "1_1") (pintype "passive"))
      (node (ref "C35") (pin "-") (pinfunction "-_-") (pintype "passive"))
      (node (ref "IC4") (pin "4") (pinfunction "V-_4") (pintype "power_in"))
      (node (ref "R33") (pin "1") (pinfunction "1_1") (pintype "passive"))
    )
    (net (code "43") (name "Net-(IC5A-BOUT)") (class "Default")
      (node (ref "IC5") (pin "8") (pinfunction "BOUT_8") (pintype "output"))
      (node (ref "R58") (pin "2") (pinfunction "2_2") (pintype "passive"))
    )
    (net (code "44") (name "Net-(IC5A-IN+)") (class "Default")
      (node (ref "IC5") (pin "2") (pinfunction "IN+_2") (pintype "input"))
      (node (ref "R54") (pin "2") (pinfunction "2_2") (pintype "passive"))
    )
    (net (code "45") (name "Net-(IC5A-IN-)") (class "Default")
      (node (ref "IC5") (pin "3") (pinfunction "IN-_3") (pintype "input"))
      (node (ref "R53") (pin "2") (pinfunction "2_2") (pintype "passive"))
      (node (ref "R58") (pin "1") (pinfunction "1_1") (pintype "passive"))
    )
    (net (code "46") (name "Net-(IC5C-V+)") (class "Default")
      (node (ref "C46") (pin "2") (pinfunction "2_2") (pintype "passive"))
      (node (ref "C48") (pin "+") (pinfunction "+_+") (pintype "passive"))
      (node (ref "IC5") (pin "1") (pinfunction "V+_1") (pintype "power_in"))
      (node (ref "R44") (pin "2") (pinfunction "2_2") (pintype "passive"))
    )
    (net (code "47") (name "Net-(IC5C-V-)") (class "Default")
      (node (ref "C47") (pin "1") (pinfunction "1_1") (pintype "passive"))
      (node (ref "C49") (pin "-") (pinfunction "-_-") (pintype "passive"))
      (node (ref "IC5") (pin "4") (pinfunction "V-_4") (pintype "power_in"))
      (node (ref "R45") (pin "1") (pinfunction "1_1") (pintype "passive"))
    )
    (net (code "48") (name "Net-(IC6A-IN+)") (class "Default")
      (node (ref "IC6") (pin "2") (pinfunction "IN+_2") (pintype "input"))
      (node (ref "R52") (pin "2") (pinfunction "2_2") (pintype "passive"))
      (node (ref "R57") (pin "1") (pinfunction "1_1") (pintype "passive"))
    )
    (net (code "49") (name "Net-(IC6A-IN-)") (class "Default")
      (node (ref "IC6") (pin "3") (pinfunction "IN-_3") (pintype "input"))
      (node (ref "R55") (pin "2") (pinfunction "2_2") (pintype "passive"))
    )
    (net (code "50") (name "Net-(IC6C-V+)") (class "Default")
      (node (ref "C39") (pin "2") (pinfunction "2_2") (pintype "passive"))
      (node (ref "C42") (pin "+") (pinfunction "+_+") (pintype "passive"))
      (node (ref "IC6") (pin "1") (pinfunction "V+_1") (pintype "power_in"))
      (node (ref "R40") (pin "2") (pinfunction "2_2") (pintype "passive"))
    )
    (net (code "51") (name "Net-(IC6C-V-)") (class "Default")
      (node (ref "C40") (pin "1") (pinfunction "1_1") (pintype "passive"))
      (node (ref "C43") (pin "-") (pinfunction "-_-") (pintype "passive"))
      (node (ref "IC6") (pin "4") (pinfunction "V-_4") (pintype "power_in"))
      (node (ref "R41") (pin "1") (pinfunction "1_1") (pintype "passive"))
    )
    (net (code "52") (name "Net-(IC7A-IN+)") (class "Default")
      (node (ref "C54") (pin "2") (pinfunction "2_2") (pintype "passive"))
      (node (ref "IC7") (pin "3") (pinfunction "IN+_3") (pintype "input"))
      (node (ref "R51") (pin "2") (pinfunction "2_2") (pintype "passive"))
    )
    (net (code "53") (name "Net-(IC7A-IN-)") (class "Default")
      (node (ref "IC7") (pin "2") (pinfunction "IN-_2") (pintype "input"))
      (node (ref "R56") (pin "2") (pinfunction "2_2") (pintype "passive"))
      (node (ref "R59") (pin "1") (pinfunction "1_1") (pintype "passive"))
    )
    (net (code "54") (name "Net-(IC7B-IN+)") (class "Default")
      (node (ref "IC7") (pin "5") (pinfunction "IN+_5") (pintype "input"))
      (node (ref "R5") (pin "2") (pinfunction "2_2") (pintype "passive"))
    )
    (net (code "55") (name "Net-(IC7B-IN-)") (class "Default")
      (node (ref "IC7") (pin "6") (pinfunction "IN-_6") (pintype "input"))
      (node (ref "R3") (pin "2") (pinfunction "2_2") (pintype "passive"))
      (node (ref "R7") (pin "2") (pinfunction "2_2") (pintype "passive"))
      (node (ref "R8") (pin "2") (pinfunction "2_2") (pintype "passive"))
    )
    (net (code "56") (name "Net-(IC7B-OUT)") (class "Default")
      (node (ref "D5") (pin "A") (pinfunction "A_A") (pintype "passive"))
      (node (ref "D6") (pin "A") (pinfunction "A_A") (pintype "passive"))
      (node (ref "D7") (pin "A") (pinfunction "A_A") (pintype "passive"))
      (node (ref "IC7") (pin "7") (pinfunction "OUT_7") (pintype "output"))
      (node (ref "R15") (pin "1") (pinfunction "1_1") (pintype "passive"))
    )
    (net (code "57") (name "Net-(IC7C-V+)") (class "Default")
      (node (ref "C21") (pin "2") (pinfunction "2_2") (pintype "passive"))
      (node (ref "C23") (pin "+") (pinfunction "+_+") (pintype "passive"))
      (node (ref "IC7") (pin "8") (pinfunction "V+_8") (pintype "power_in"))
      (node (ref "R23") (pin "2") (pinfunction "2_2") (pintype "passive"))
    )
    (net (code "58") (name "Net-(IC7C-V-)") (class "Default")
      (node (ref "C22") (pin "1") (pinfunction "1_1") (pintype "passive"))
      (node (ref "C24") (pin "-") (pinfunction "-_-") (pintype "passive"))
      (node (ref "IC7") (pin "4") (pinfunction "V-_4") (pintype "power_in"))
      (node (ref "R24") (pin "1") (pinfunction "1_1") (pintype "passive"))
    )
    (net (code "59") (name "Net-(LED1-PadA)") (class "Default")
      (node (ref "LED1") (pin "A") (pinfunction "A_A") (pintype "passive"))
      (node (ref "R1") (pin "1") (pinfunction "1_1") (pintype "passive"))
    )
    (net (code "60") (name "Net-(LED2-PadA)") (class "Default")
      (node (ref "LED2") (pin "A") (pinfunction "A_A") (pintype "passive"))
      (node (ref "R2") (pin "1") (pinfunction "1_1") (pintype "passive"))
    )
    (net (code "61") (name "Net-(LED3-PadA)") (class "Default")
      (node (ref "LED3") (pin "A") (pinfunction "A_A") (pintype "passive"))
      (node (ref "R11") (pin "1") (pinfunction "1_1") (pintype "passive"))
    )
    (net (code "62") (name "Net-(LED4-PadA)") (class "Default")
      (node (ref "LED4") (pin "A") (pinfunction "A_A") (pintype "passive"))
      (node (ref "R12") (pin "1") (pinfunction "1_1") (pintype "passive"))
    )
    (net (code "63") (name "Net-(LED5-PadC)") (class "Default")
      (node (ref "LED5") (pin "C") (pinfunction "C_C") (pintype "passive"))
      (node (ref "R16") (pin "2") (pinfunction "2_2") (pintype "passive"))
    )
    (net (code "64") (name "Net-(LED6-PadC)") (class "Default")
      (node (ref "LED6") (pin "C") (pinfunction "C_C") (pintype "passive"))
      (node (ref "R17") (pin "2") (pinfunction "2_2") (pintype "passive"))
    )
    (net (code "65") (name "PULSE_DURATION") (class "Default")
      (node (ref "IC5") (pin "7") (pinfunction "OUT_7") (pintype "output"))
      (node (ref "X3") (pin "3") (pinfunction "S_3") (pintype "passive"))
      (node (ref "X3") (pin "7") (pinfunction "S_7") (pintype "passive"))
    )
    (net (code "66") (name "RESET") (class "Default")
      (node (ref "IC2") (pin "4") (pinfunction "IN_4") (pintype "input"))
      (node (ref "X3") (pin "4") (pinfunction "S_4") (pintype "passive"))
      (node (ref "X3") (pin "8") (pinfunction "S_8") (pintype "passive"))
    )
    (net (code "67") (name "RISING_SLOPE") (class "Default")
      (node (ref "IC6") (pin "7") (pinfunction "OUT_7") (pintype "output"))
      (node (ref "R57") (pin "2") (pinfunction "2_2") (pintype "passive"))
      (node (ref "X3") (pin "2") (pinfunction "S_2") (pintype "passive"))
      (node (ref "X3") (pin "6") (pinfunction "S_6") (pintype "passive"))
    )
    (net (code "68") (name "SIGNAL_INPUT") (class "Default")
      (node (ref "A1") (pin "ANT") (pinfunction "ANT_ANT") (pintype "bidirectional"))
      (node (ref "R19") (pin "1") (pinfunction "1_1") (pintype "passive"))
    )
    (net (code "69") (name "unconnected-(IC6A-BOUT-Pad8)") (class "Default")
      (node (ref "IC6") (pin "8") (pinfunction "BOUT_8") (pintype "output"))
    )
  )
)
